# li-ov5640-mipi-af.net
KiCad netlist of a schematic drawn in Altium Designer
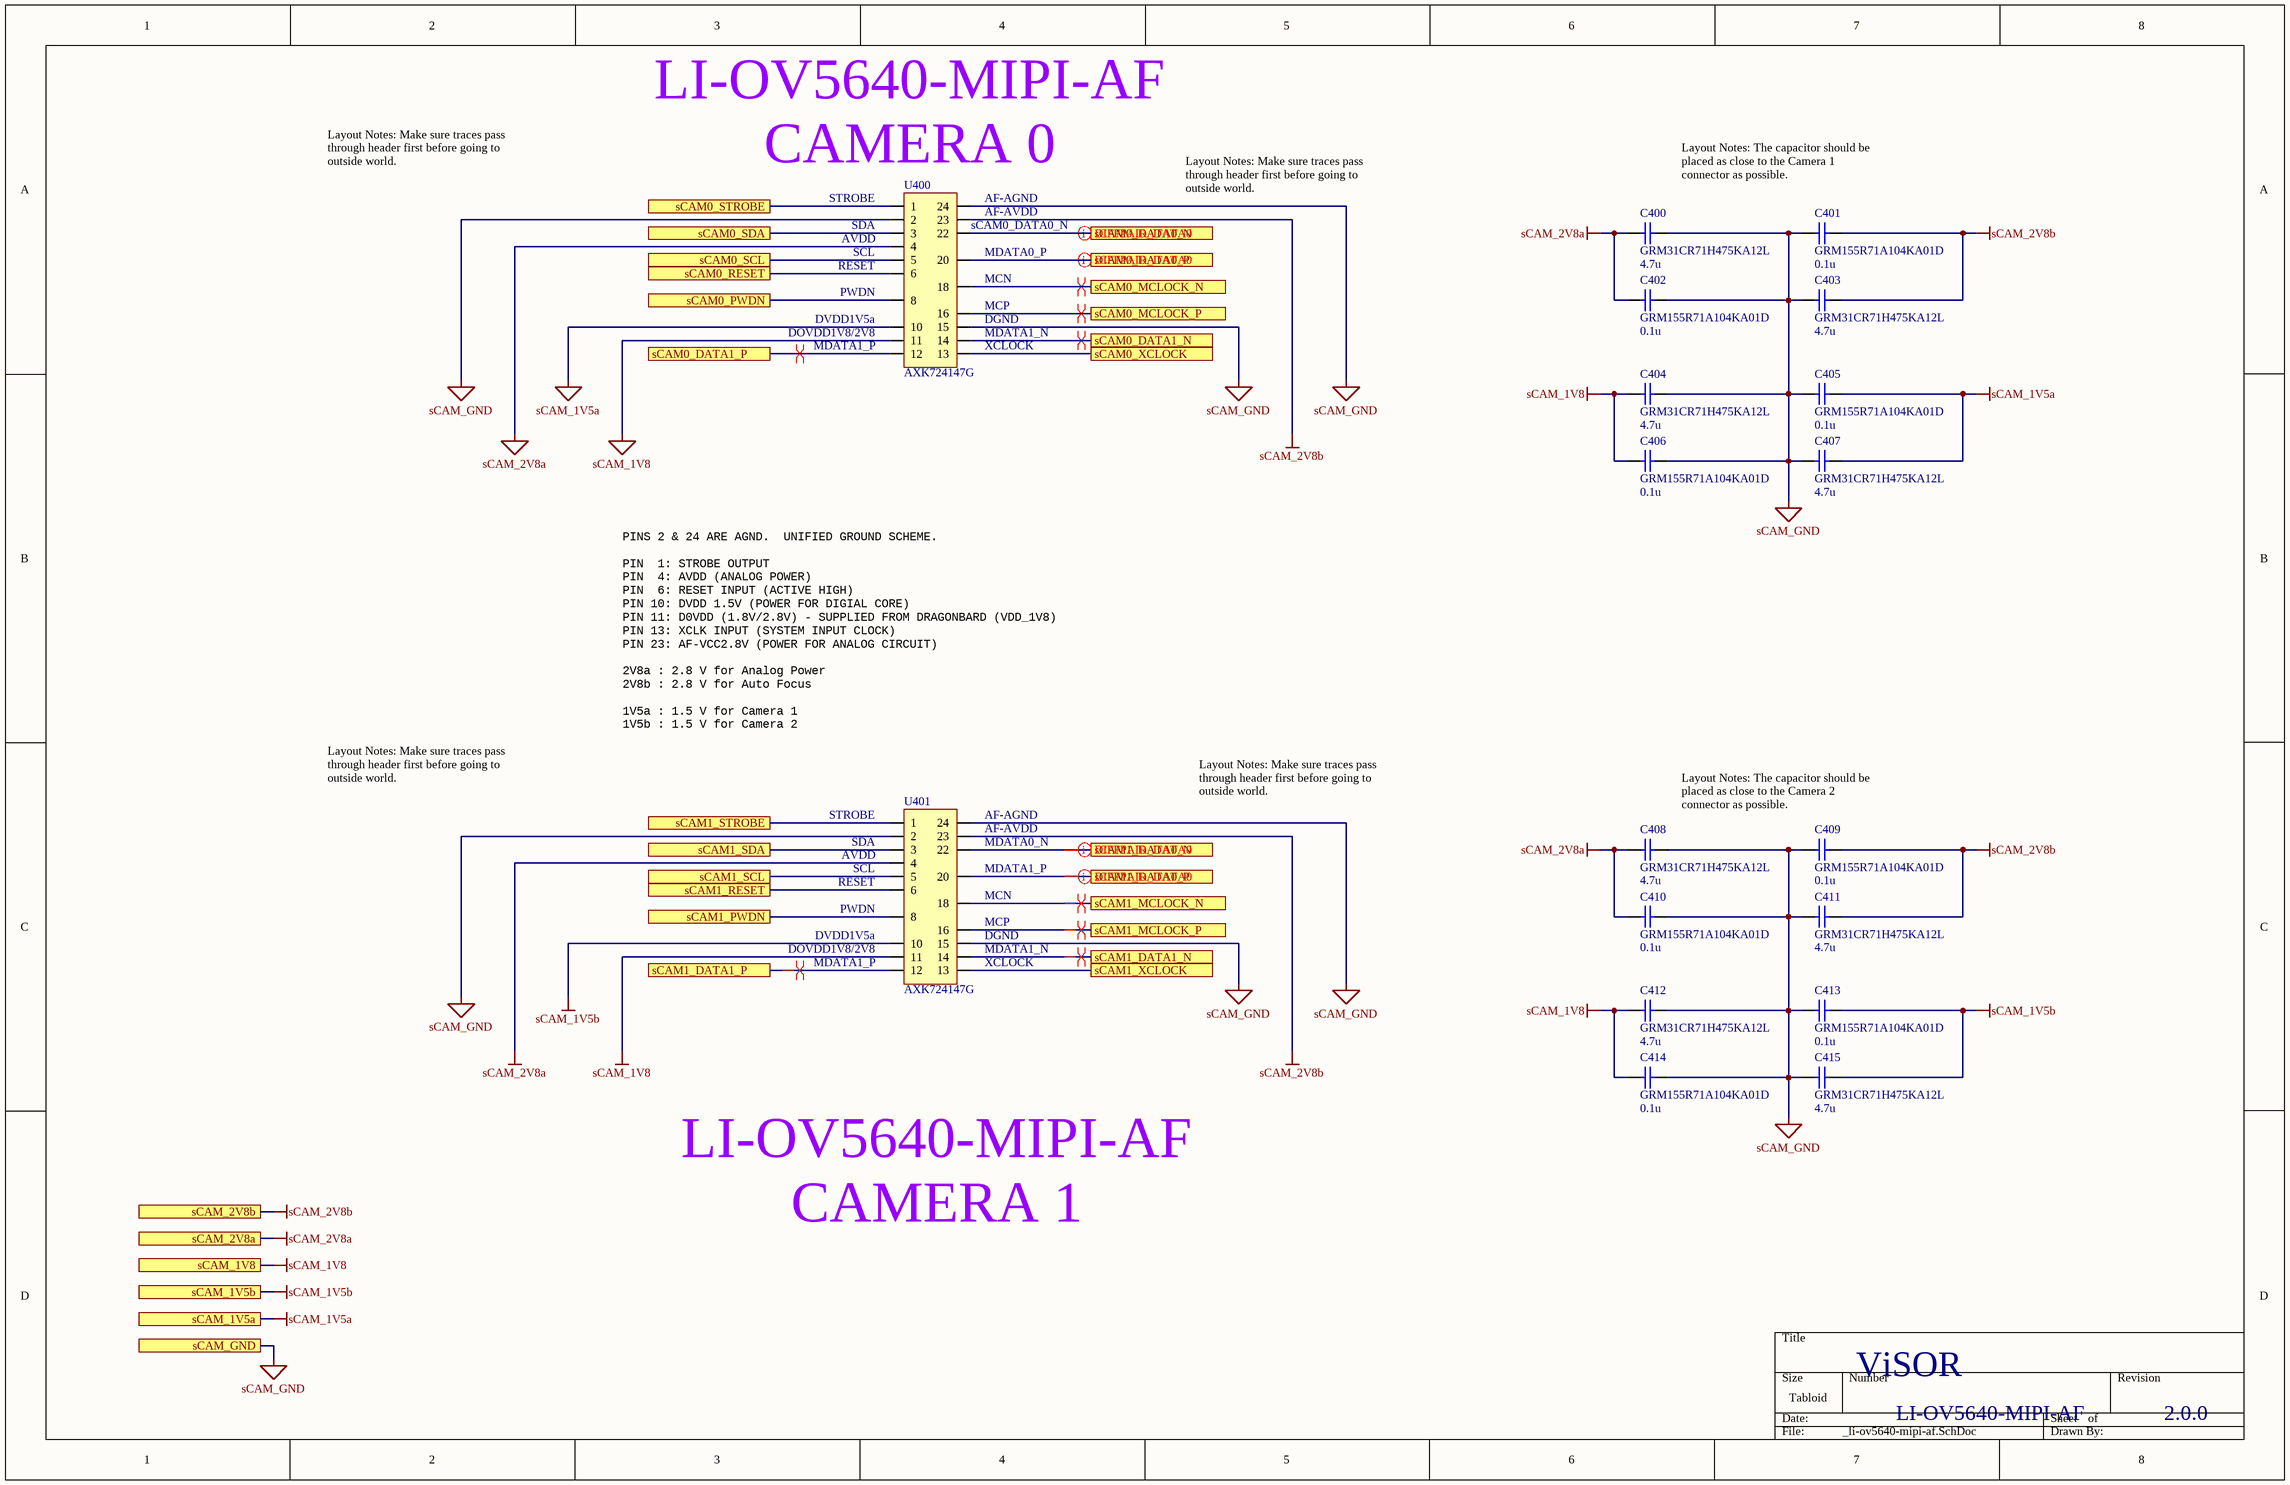
[diagram p0: _li-ov5640-mipi-af.SchDoc]

(export (version "E")
  (design (tool "Eeschema 10.0.6"))
  (components
    (comp (ref "C400")
      (value "GRM31CR71H475KA12L")
      (footprint "1206")
      (description "-55-125C, 3216, 50V, X7R, ±10%")
      (fields (field (name "ALTIUM_VALUE") "4.7u"))
      (libsource (lib "standard_capacitors") (part "GRM31CR71HxxxKdddd"))
    )
    (comp (ref "C401")
      (value "GRM155R71A104KA01D")
      (footprint "0402")
      (description "-55-125C, 1005, 10V, X7R, ±10%")
      (fields (field (name "ALTIUM_VALUE") "0.1u"))
      (libsource (lib "standard_capacitors") (part "GRM155R71AxxxKdddd"))
    )
    (comp (ref "C402")
      (value "GRM155R71A104KA01D")
      (footprint "0402")
      (description "-55-125C, 1005, 10V, X7R, ±10%")
      (fields (field (name "ALTIUM_VALUE") "0.1u"))
      (libsource (lib "standard_capacitors") (part "GRM155R71AxxxKdddd"))
    )
    (comp (ref "C403")
      (value "GRM31CR71H475KA12L")
      (footprint "1206")
      (description "-55-125C, 3216, 50V, X7R, ±10%")
      (fields (field (name "ALTIUM_VALUE") "4.7u"))
      (libsource (lib "standard_capacitors") (part "GRM31CR71HxxxKdddd"))
    )
    (comp (ref "C404")
      (value "GRM31CR71H475KA12L")
      (footprint "1206")
      (description "-55-125C, 3216, 50V, X7R, ±10%")
      (fields (field (name "ALTIUM_VALUE") "4.7u"))
      (libsource (lib "standard_capacitors") (part "GRM31CR71HxxxKdddd"))
    )
    (comp (ref "C405")
      (value "GRM155R71A104KA01D")
      (footprint "0402")
      (description "-55-125C, 1005, 10V, X7R, ±10%")
      (fields (field (name "ALTIUM_VALUE") "0.1u"))
      (libsource (lib "standard_capacitors") (part "GRM155R71AxxxKdddd"))
    )
    (comp (ref "C406")
      (value "GRM155R71A104KA01D")
      (footprint "0402")
      (description "-55-125C, 1005, 10V, X7R, ±10%")
      (fields (field (name "ALTIUM_VALUE") "0.1u"))
      (libsource (lib "standard_capacitors") (part "GRM155R71AxxxKdddd"))
    )
    (comp (ref "C407")
      (value "GRM31CR71H475KA12L")
      (footprint "1206")
      (description "-55-125C, 3216, 50V, X7R, ±10%")
      (fields (field (name "ALTIUM_VALUE") "4.7u"))
      (libsource (lib "standard_capacitors") (part "GRM31CR71HxxxKdddd"))
    )
    (comp (ref "C408")
      (value "GRM31CR71H475KA12L")
      (footprint "1206")
      (description "-55-125C, 3216, 50V, X7R, ±10%")
      (fields (field (name "ALTIUM_VALUE") "4.7u"))
      (libsource (lib "standard_capacitors") (part "GRM31CR71HxxxKdddd"))
    )
    (comp (ref "C409")
      (value "GRM155R71A104KA01D")
      (footprint "0402")
      (description "-55-125C, 1005, 10V, X7R, ±10%")
      (fields (field (name "ALTIUM_VALUE") "0.1u"))
      (libsource (lib "standard_capacitors") (part "GRM155R71AxxxKdddd"))
    )
    (comp (ref "C410")
      (value "GRM155R71A104KA01D")
      (footprint "0402")
      (description "-55-125C, 1005, 10V, X7R, ±10%")
      (fields (field (name "ALTIUM_VALUE") "0.1u"))
      (libsource (lib "standard_capacitors") (part "GRM155R71AxxxKdddd"))
    )
    (comp (ref "C411")
      (value "GRM31CR71H475KA12L")
      (footprint "1206")
      (description "-55-125C, 3216, 50V, X7R, ±10%")
      (fields (field (name "ALTIUM_VALUE") "4.7u"))
      (libsource (lib "standard_capacitors") (part "GRM31CR71HxxxKdddd"))
    )
    (comp (ref "C412")
      (value "GRM31CR71H475KA12L")
      (footprint "1206")
      (description "-55-125C, 3216, 50V, X7R, ±10%")
      (fields (field (name "ALTIUM_VALUE") "4.7u"))
      (libsource (lib "standard_capacitors") (part "GRM31CR71HxxxKdddd"))
    )
    (comp (ref "C413")
      (value "GRM155R71A104KA01D")
      (footprint "0402")
      (description "-55-125C, 1005, 10V, X7R, ±10%")
      (fields (field (name "ALTIUM_VALUE") "0.1u"))
      (libsource (lib "standard_capacitors") (part "GRM155R71AxxxKdddd"))
    )
    (comp (ref "C414")
      (value "GRM155R71A104KA01D")
      (footprint "0402")
      (description "-55-125C, 1005, 10V, X7R, ±10%")
      (fields (field (name "ALTIUM_VALUE") "0.1u"))
      (libsource (lib "standard_capacitors") (part "GRM155R71AxxxKdddd"))
    )
    (comp (ref "C415")
      (value "GRM31CR71H475KA12L")
      (footprint "1206")
      (description "-55-125C, 3216, 50V, X7R, ±10%")
      (fields (field (name "ALTIUM_VALUE") "4.7u"))
      (libsource (lib "standard_capacitors") (part "GRM31CR71HxxxKdddd"))
    )
    (comp (ref "U400")
      (value "AXK724147G")
      (footprint "AXK724147G")
      (description "CONN SOCKET P4 .4MM 24POS SMD")
      (libsource (lib "panasonic") (part "AXK724147G"))
    )
    (comp (ref "U401")
      (value "AXK724147G")
      (footprint "AXK724147G")
      (description "CONN SOCKET P4 .4MM 24POS SMD")
      (libsource (lib "panasonic") (part "AXK724147G"))
    )
  )
  (nets
    (net (code "1") (name "/sCAM0_DATA0_N") (class "Default")
      (node (ref "U400") (pin "22") (pinfunction "22_22") (pintype "passive"))
    )
    (net (code "2") (name "/sCAM0_DATA0_P") (class "Default")
      (node (ref "U400") (pin "20") (pinfunction "20_20") (pintype "passive"))
    )
    (net (code "3") (name "/sCAM0_DATA1_N") (class "Default")
      (node (ref "U400") (pin "14") (pinfunction "14_14") (pintype "passive"))
    )
    (net (code "4") (name "/sCAM0_DATA1_P") (class "Default")
      (node (ref "U400") (pin "12") (pinfunction "12_12") (pintype "passive"))
    )
    (net (code "5") (name "/sCAM0_MCLOCK_N") (class "Default")
      (node (ref "U400") (pin "18") (pinfunction "18_18") (pintype "passive"))
    )
    (net (code "6") (name "/sCAM0_MCLOCK_P") (class "Default")
      (node (ref "U400") (pin "16") (pinfunction "16_16") (pintype "passive"))
    )
    (net (code "7") (name "/sCAM0_PWDN") (class "Default")
      (node (ref "U400") (pin "8") (pinfunction "8_8") (pintype "passive"))
    )
    (net (code "8") (name "/sCAM0_RESET") (class "Default")
      (node (ref "U400") (pin "6") (pinfunction "6_6") (pintype "passive"))
    )
    (net (code "9") (name "/sCAM0_SCL") (class "Default")
      (node (ref "U400") (pin "5") (pinfunction "5_5") (pintype "passive"))
    )
    (net (code "10") (name "/sCAM0_SDA") (class "Default")
      (node (ref "U400") (pin "3") (pinfunction "3_3") (pintype "passive"))
    )
    (net (code "11") (name "/sCAM0_STROBE") (class "Default")
      (node (ref "U400") (pin "1") (pinfunction "1_1") (pintype "passive"))
    )
    (net (code "12") (name "/sCAM0_XCLOCK") (class "Default")
      (node (ref "U400") (pin "13") (pinfunction "13_13") (pintype "passive"))
    )
    (net (code "13") (name "/sCAM1_DATA0_N") (class "Default")
      (node (ref "U401") (pin "22") (pinfunction "22_22") (pintype "passive"))
    )
    (net (code "14") (name "/sCAM1_DATA0_P") (class "Default")
      (node (ref "U401") (pin "20") (pinfunction "20_20") (pintype "passive"))
    )
    (net (code "15") (name "/sCAM1_DATA1_N") (class "Default")
      (node (ref "U401") (pin "14") (pinfunction "14_14") (pintype "passive"))
    )
    (net (code "16") (name "/sCAM1_DATA1_P") (class "Default")
      (node (ref "U401") (pin "12") (pinfunction "12_12") (pintype "passive"))
    )
    (net (code "17") (name "/sCAM1_MCLOCK_N") (class "Default")
      (node (ref "U401") (pin "18") (pinfunction "18_18") (pintype "passive"))
    )
    (net (code "18") (name "/sCAM1_MCLOCK_P") (class "Default")
      (node (ref "U401") (pin "16") (pinfunction "16_16") (pintype "passive"))
    )
    (net (code "19") (name "/sCAM1_PWDN") (class "Default")
      (node (ref "U401") (pin "8") (pinfunction "8_8") (pintype "passive"))
    )
    (net (code "20") (name "/sCAM1_RESET") (class "Default")
      (node (ref "U401") (pin "6") (pinfunction "6_6") (pintype "passive"))
    )
    (net (code "21") (name "/sCAM1_SCL") (class "Default")
      (node (ref "U401") (pin "5") (pinfunction "5_5") (pintype "passive"))
    )
    (net (code "22") (name "/sCAM1_SDA") (class "Default")
      (node (ref "U401") (pin "3") (pinfunction "3_3") (pintype "passive"))
    )
    (net (code "23") (name "/sCAM1_STROBE") (class "Default")
      (node (ref "U401") (pin "1") (pinfunction "1_1") (pintype "passive"))
    )
    (net (code "24") (name "/sCAM1_XCLOCK") (class "Default")
      (node (ref "U401") (pin "13") (pinfunction "13_13") (pintype "passive"))
    )
    (net (code "25") (name "sCAM_1V5a") (class "Default")
      (node (ref "C405") (pin "2") (pinfunction "2_2") (pintype "passive"))
      (node (ref "C407") (pin "1") (pinfunction "1_1") (pintype "passive"))
      (node (ref "U400") (pin "10") (pinfunction "10_10") (pintype "passive"))
    )
    (net (code "26") (name "sCAM_1V5b") (class "Default")
      (node (ref "C413") (pin "2") (pinfunction "2_2") (pintype "passive"))
      (node (ref "C415") (pin "1") (pinfunction "1_1") (pintype "passive"))
      (node (ref "U401") (pin "10") (pinfunction "10_10") (pintype "passive"))
    )
    (net (code "27") (name "sCAM_1V8") (class "Default")
      (node (ref "C404") (pin "1") (pinfunction "1_1") (pintype "passive"))
      (node (ref "C406") (pin "2") (pinfunction "2_2") (pintype "passive"))
      (node (ref "C412") (pin "1") (pinfunction "1_1") (pintype "passive"))
      (node (ref "C414") (pin "2") (pinfunction "2_2") (pintype "passive"))
      (node (ref "U400") (pin "11") (pinfunction "11_11") (pintype "passive"))
      (node (ref "U401") (pin "11") (pinfunction "11_11") (pintype "passive"))
    )
    (net (code "28") (name "sCAM_2V8a") (class "Default")
      (node (ref "C400") (pin "1") (pinfunction "1_1") (pintype "passive"))
      (node (ref "C402") (pin "2") (pinfunction "2_2") (pintype "passive"))
      (node (ref "C408") (pin "1") (pinfunction "1_1") (pintype "passive"))
      (node (ref "C410") (pin "2") (pinfunction "2_2") (pintype "passive"))
      (node (ref "U400") (pin "4") (pinfunction "4_4") (pintype "passive"))
      (node (ref "U401") (pin "4") (pinfunction "4_4") (pintype "passive"))
    )
    (net (code "29") (name "sCAM_2V8b") (class "Default")
      (node (ref "C401") (pin "2") (pinfunction "2_2") (pintype "passive"))
      (node (ref "C403") (pin "1") (pinfunction "1_1") (pintype "passive"))
      (node (ref "C409") (pin "2") (pinfunction "2_2") (pintype "passive"))
      (node (ref "C411") (pin "1") (pinfunction "1_1") (pintype "passive"))
      (node (ref "U400") (pin "23") (pinfunction "23_23") (pintype "passive"))
      (node (ref "U401") (pin "23") (pinfunction "23_23") (pintype "passive"))
    )
    (net (code "30") (name "sCAM_GND") (class "Default")
      (node (ref "C400") (pin "2") (pinfunction "2_2") (pintype "passive"))
      (node (ref "C401") (pin "1") (pinfunction "1_1") (pintype "passive"))
      (node (ref "C402") (pin "1") (pinfunction "1_1") (pintype "passive"))
      (node (ref "C403") (pin "2") (pinfunction "2_2") (pintype "passive"))
      (node (ref "C404") (pin "2") (pinfunction "2_2") (pintype "passive"))
      (node (ref "C405") (pin "1") (pinfunction "1_1") (pintype "passive"))
      (node (ref "C406") (pin "1") (pinfunction "1_1") (pintype "passive"))
      (node (ref "C407") (pin "2") (pinfunction "2_2") (pintype "passive"))
      (node (ref "C408") (pin "2") (pinfunction "2_2") (pintype "passive"))
      (node (ref "C409") (pin "1") (pinfunction "1_1") (pintype "passive"))
      (node (ref "C410") (pin "1") (pinfunction "1_1") (pintype "passive"))
      (node (ref "C411") (pin "2") (pinfunction "2_2") (pintype "passive"))
      (node (ref "C412") (pin "2") (pinfunction "2_2") (pintype "passive"))
      (node (ref "C413") (pin "1") (pinfunction "1_1") (pintype "passive"))
      (node (ref "C414") (pin "1") (pinfunction "1_1") (pintype "passive"))
      (node (ref "C415") (pin "2") (pinfunction "2_2") (pintype "passive"))
      (node (ref "U400") (pin "15") (pinfunction "15_15") (pintype "passive"))
      (node (ref "U400") (pin "2") (pinfunction "2_2") (pintype "passive"))
      (node (ref "U400") (pin "24") (pinfunction "24_24") (pintype "passive"))
      (node (ref "U401") (pin "15") (pinfunction "15_15") (pintype "passive"))
      (node (ref "U401") (pin "2") (pinfunction "2_2") (pintype "passive"))
      (node (ref "U401") (pin "24") (pinfunction "24_24") (pintype "passive"))
    )
    (net (code "31") (name "unconnected-(U400-Pad7)") (class "Default")
      (node (ref "U400") (pin "7") (pinfunction "7_7") (pintype "passive"))
    )
    (net (code "32") (name "unconnected-(U400-Pad9)") (class "Default")
      (node (ref "U400") (pin "9") (pinfunction "9_9") (pintype "passive"))
    )
    (net (code "33") (name "unconnected-(U400-Pad17)") (class "Default")
      (node (ref "U400") (pin "17") (pinfunction "17_17") (pintype "passive"))
    )
    (net (code "34") (name "unconnected-(U400-Pad19)") (class "Default")
      (node (ref "U400") (pin "19") (pinfunction "19_19") (pintype "passive"))
    )
    (net (code "35") (name "unconnected-(U400-Pad21)") (class "Default")
      (node (ref "U400") (pin "21") (pinfunction "21_21") (pintype "passive"))
    )
    (net (code "36") (name "unconnected-(U401-Pad7)") (class "Default")
      (node (ref "U401") (pin "7") (pinfunction "7_7") (pintype "passive"))
    )
    (net (code "37") (name "unconnected-(U401-Pad9)") (class "Default")
      (node (ref "U401") (pin "9") (pinfunction "9_9") (pintype "passive"))
    )
    (net (code "38") (name "unconnected-(U401-Pad17)") (class "Default")
      (node (ref "U401") (pin "17") (pinfunction "17_17") (pintype "passive"))
    )
    (net (code "39") (name "unconnected-(U401-Pad19)") (class "Default")
      (node (ref "U401") (pin "19") (pinfunction "19_19") (pintype "passive"))
    )
    (net (code "40") (name "unconnected-(U401-Pad21)") (class "Default")
      (node (ref "U401") (pin "21") (pinfunction "21_21") (pintype "passive"))
    )
  )
)
